# PSU_MAX8860_ADJ.net
KiCad netlist of a schematic drawn in Altium Designer
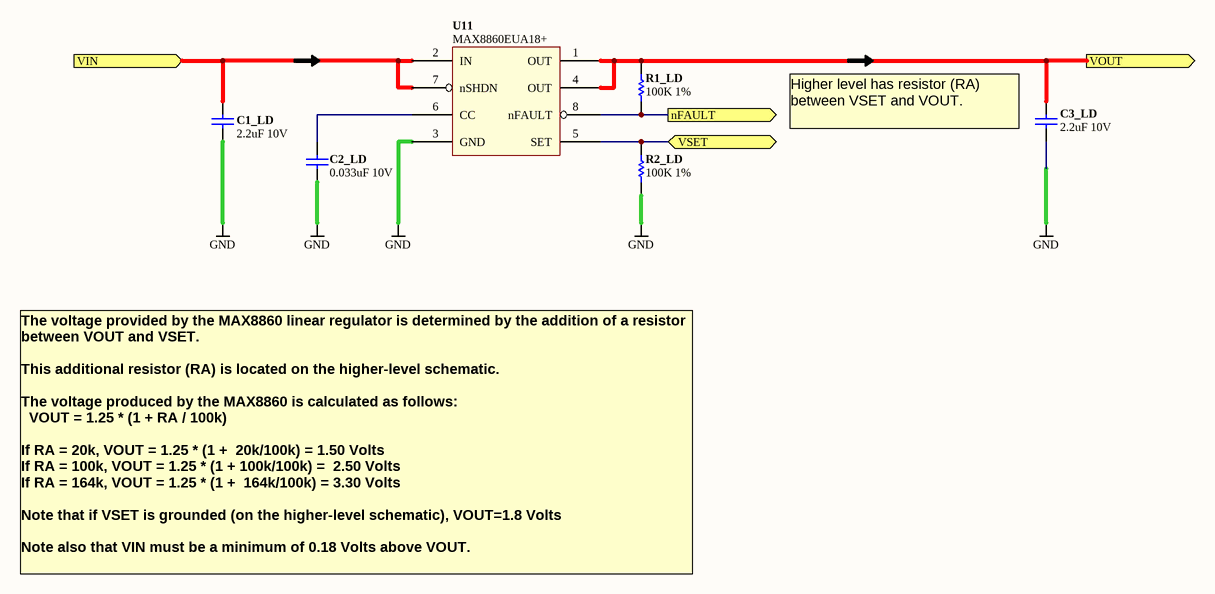
[diagram p0: PSU_MAX8860_ADJ.SchDoc]

(export (version "E")
  (design (tool "Eeschema 10.0.6"))
  (components
    (comp (ref "C1_LD")
      (value "2.2uF 10V")
      (footprint "CAPC1608-STAR")
      (description "Capacitor, Ceramic, 2.2uF 10% 10V 0603 (1608) X5R")
      (fields (field (name "TOLERANCE") "10 %"))
      (libsource (lib "AltiumDesignLibrary") (part "CAP-NP"))
    )
    (comp (ref "C2_LD")
      (value "0.033uF 10V")
      (footprint "CAPC1005-STAR")
      (description "Capacitor, Ceramic, 0.033uF 10% 10V 0402 (1005) X7R")
      (fields (field (name "TOLERANCE") "10 %"))
      (libsource (lib "AltiumDesignLibrary") (part "CAP-NP"))
    )
    (comp (ref "C3_LD")
      (value "2.2uF 10V")
      (footprint "CAPC1608-STAR")
      (description "Capacitor, Ceramic, 2.2uF 10% 10V 0603 (1608) X5R")
      (fields (field (name "TOLERANCE") "10 %"))
      (libsource (lib "AltiumDesignLibrary") (part "CAP-NP"))
    )
    (comp (ref "R1_LD")
      (value "100K 1%")
      (footprint "RESC1005-STAR")
      (description "Resistor, 100K 1% 0402 (1005)")
      (fields (field (name "TOLERANCE") "1 %"))
      (libsource (lib "AltiumDesignLibrary") (part "RES"))
    )
    (comp (ref "R2_LD")
      (value "100K 1%")
      (footprint "RESC1005-STAR")
      (description "Resistor, 100K 1% 0402 (1005)")
      (fields (field (name "TOLERANCE") "1 %"))
      (libsource (lib "AltiumDesignLibrary") (part "RES"))
    )
    (comp (ref "U11")
      (value "MAX8860EUA18+")
      (footprint "SOP65P490-8")
      (description "MAX8860EUA18+, 1.8V Linear Regulator with adjustable Output, Low-noise, Low-dropout, 300mA, uMAX")
      (libsource (lib "AltiumDesignLibrary") (part "MAX8860"))
    )
  )
  (nets
    (net (code "1") (name "/VIN") (class "Default")
      (node (ref "C1_LD") (pin "1") (pinfunction "1_1") (pintype "passive"))
      (node (ref "U11") (pin "2") (pinfunction "IN_2") (pintype "passive"))
      (node (ref "U11") (pin "7") (pinfunction "nSHDN_7") (pintype "passive"))
    )
    (net (code "2") (name "/VOUT") (class "Default")
      (node (ref "C3_LD") (pin "1") (pinfunction "1_1") (pintype "passive"))
      (node (ref "R1_LD") (pin "1") (pinfunction "1_1") (pintype "passive"))
      (node (ref "U11") (pin "1") (pinfunction "OUT_1") (pintype "passive"))
      (node (ref "U11") (pin "4") (pinfunction "OUT_4") (pintype "passive"))
    )
    (net (code "3") (name "/VSET") (class "Default")
      (node (ref "R2_LD") (pin "1") (pinfunction "1_1") (pintype "passive"))
      (node (ref "U11") (pin "5") (pinfunction "SET_5") (pintype "passive"))
    )
    (net (code "4") (name "/nFAULT") (class "Default")
      (node (ref "R1_LD") (pin "2") (pinfunction "2_2") (pintype "passive"))
      (node (ref "U11") (pin "8") (pinfunction "nFAULT_8") (pintype "passive"))
    )
    (net (code "5") (name "GND") (class "Default")
      (node (ref "C1_LD") (pin "2") (pinfunction "2_2") (pintype "passive"))
      (node (ref "C2_LD") (pin "2") (pinfunction "2_2") (pintype "passive"))
      (node (ref "C3_LD") (pin "2") (pinfunction "2_2") (pintype "passive"))
      (node (ref "R2_LD") (pin "2") (pinfunction "2_2") (pintype "passive"))
      (node (ref "U11") (pin "3") (pinfunction "GND_3") (pintype "passive"))
    )
    (net (code "6") (name "Net-(U11-CC)") (class "Default")
      (node (ref "C2_LD") (pin "1") (pinfunction "1_1") (pintype "passive"))
      (node (ref "U11") (pin "6") (pinfunction "CC_6") (pintype "passive"))
    )
  )
)
